# 7V_5V_3V3_Bucks.net
KiCad netlist of a schematic drawn in Altium Designer
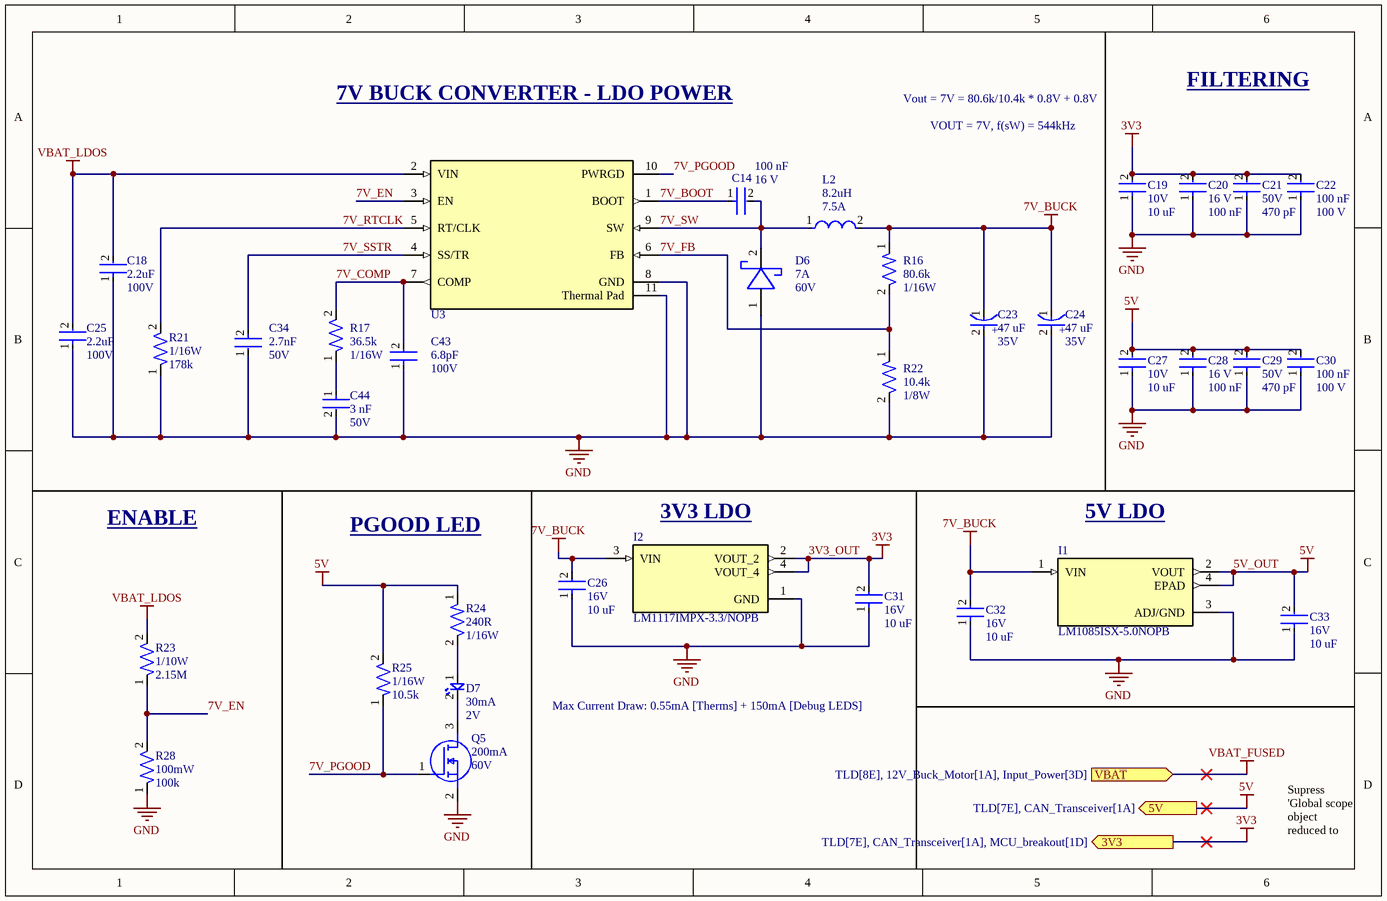
[diagram p0: 7V_5V_3V3_Bucks.SchDoc]

(export (version "E")
  (design (tool "Eeschema 10.0.6"))
  (components
    (comp (ref "C14")
      (value "CC0402KRX7R7BB104")
      (footprint "CAP-0402")
      (description "CAP CER 0.1UF 16V X7R 0402")
      (fields (field (name "VOLTAGE RATING") "16 V") (field (name "CAPACITANCE") "100 nF"))
      (libsource (lib "JLC_25") (part "CAP-0.1U-0001"))
    )
    (comp (ref "C18")
      (value "CC1206KKX7R0BB225")
      (footprint "CAP-1206")
      (description "CAP CER 2.2UF 100V X7R 1206")
      (fields (field (name "CAPACITANCE") "2.2uF") (field (name "VOLTAGE") "100V"))
      (libsource (lib "JLC_25") (part "CAP-2.2U-0001"))
    )
    (comp (ref "C19")
      (value "CC0603KRX5R6BB106")
      (footprint "CAP-0603")
      (description "CAP CER 10UF 10V X5R 0603")
      (fields (field (name "VOLTAGE") "10V") (field (name "CAPACITANCE") "10 uF"))
      (libsource (lib "JLC_25") (part "CAP-10U-0001"))
    )
    (comp (ref "C20")
      (value "CC0402KRX7R7BB104")
      (footprint "CAP-0402")
      (description "CAP CER 0.1UF 16V X7R 0402")
      (fields (field (name "VOLTAGE RATING") "16 V") (field (name "CAPACITANCE") "100 nF"))
      (libsource (lib "JLC_25") (part "CAP-0.1U-0001"))
    )
    (comp (ref "C21")
      (value "CC0805JRNPO9BN471")
      (footprint "CAP-0805")
      (description "CAP CER 470PF 50V C0G/NPO 0805")
      (fields (field (name "VOLTAGE") "50V") (field (name "CAPACITANCE") "470 pF"))
      (libsource (lib "JLC_25") (part "CAP-470P-0001"))
    )
    (comp (ref "C22")
      (value "CC0603KRX7R0BB104")
      (footprint "CAP-0603")
      (description "CAP CER 0.1UF 100V X7R 0603")
      (fields (field (name "CAPACITANCE") "100 nF") (field (name "VOLTAGE") "100 V"))
      (libsource (lib "JLC_25") (part "CAP-100N-0001"))
    )
    (comp (ref "C23")
      (value "EEH-ZC1V470P")
      (footprint "CAP-Radial-SMD")
      (description "CAP ALUM HYBRID 47UF 20% 35V SMD")
      (fields (field (name "CAPACITANCE") "47 uF") (field (name "VOLTAGE") "35V"))
      (libsource (lib "JLC_25") (part "CAP-47U-0002"))
    )
    (comp (ref "C24")
      (value "EEH-ZC1V470P")
      (footprint "CAP-Radial-SMD")
      (description "CAP ALUM HYBRID 47UF 20% 35V SMD")
      (fields (field (name "CAPACITANCE") "47 uF") (field (name "VOLTAGE") "35V"))
      (libsource (lib "JLC_25") (part "CAP-47U-0002"))
    )
    (comp (ref "C25")
      (value "CC1206KKX7R0BB225")
      (footprint "CAP-1206")
      (description "CAP CER 2.2UF 100V X7R 1206")
      (fields (field (name "CAPACITANCE") "2.2uF") (field (name "VOLTAGE") "100V"))
      (libsource (lib "JLC_25") (part "CAP-2.2U-0001"))
    )
    (comp (ref "C26")
      (value "293D106X9016A2TE3")
      (footprint "CAP-1210")
      (description "CAP TANT 10UF 10% 16V 1206")
      (fields (field (name "VOLTAGE") "16V") (field (name "CAPACITANCE") "10 uF"))
      (libsource (lib "JLC_25") (part "CAP-10U-0003_1"))
    )
    (comp (ref "C27")
      (value "CC0603KRX5R6BB106")
      (footprint "CAP-0603")
      (description "CAP CER 10UF 10V X5R 0603")
      (fields (field (name "VOLTAGE") "10V") (field (name "CAPACITANCE") "10 uF"))
      (libsource (lib "JLC_25") (part "CAP-10U-0001"))
    )
    (comp (ref "C28")
      (value "CC0402KRX7R7BB104")
      (footprint "CAP-0402")
      (description "CAP CER 0.1UF 16V X7R 0402")
      (fields (field (name "VOLTAGE RATING") "16 V") (field (name "CAPACITANCE") "100 nF"))
      (libsource (lib "JLC_25") (part "CAP-0.1U-0001"))
    )
    (comp (ref "C29")
      (value "CC0805JRNPO9BN471")
      (footprint "CAP-0805")
      (description "CAP CER 470PF 50V C0G/NPO 0805")
      (fields (field (name "VOLTAGE") "50V") (field (name "CAPACITANCE") "470 pF"))
      (libsource (lib "JLC_25") (part "CAP-470P-0001"))
    )
    (comp (ref "C30")
      (value "CC0603KRX7R0BB104")
      (footprint "CAP-0603")
      (description "CAP CER 0.1UF 100V X7R 0603")
      (fields (field (name "CAPACITANCE") "100 nF") (field (name "VOLTAGE") "100 V"))
      (libsource (lib "JLC_25") (part "CAP-100N-0001"))
    )
    (comp (ref "C31")
      (value "293D106X9016A2TE3")
      (footprint "CAP-1210")
      (description "CAP TANT 10UF 10% 16V 1206")
      (fields (field (name "VOLTAGE") "16V") (field (name "CAPACITANCE") "10 uF"))
      (libsource (lib "JLC_25") (part "CAP-10U-0003_1"))
    )
    (comp (ref "C32")
      (value "293D106X9016A2TE3")
      (footprint "CAP-1210")
      (description "CAP TANT 10UF 10% 16V 1206")
      (fields (field (name "VOLTAGE") "16V") (field (name "CAPACITANCE") "10 uF"))
      (libsource (lib "JLC_25") (part "CAP-10U-0003_1"))
    )
    (comp (ref "C33")
      (value "293D106X9016A2TE3")
      (footprint "CAP-1210")
      (description "CAP TANT 10UF 10% 16V 1206")
      (fields (field (name "VOLTAGE") "16V") (field (name "CAPACITANCE") "10 uF"))
      (libsource (lib "JLC_25") (part "CAP-10U-0003_1"))
    )
    (comp (ref "C34")
      (value "GRM2165C1H272JA01D")
      (footprint "CAP-0805")
      (description "CAP CER 2700PF 50V C0G/NP0 0805")
      (fields (field (name "VOLTAGE") "50V") (field (name "CAPACITANCE") "2.7nF"))
      (libsource (lib "JLC_25") (part "CAP-2.7N-0001"))
    )
    (comp (ref "C43")
      (value "CC0603CRNPO0BN6R8")
      (footprint "CAP-0603")
      (description "CAP CER 6.8PF 100V C0G/NPO 0603")
      (fields (field (name "VOLTAGE") "100V") (field (name "CAPACITANCE") "6.8pF"))
      (libsource (lib "JLC_25") (part "CAP-6.8P-0001"))
    )
    (comp (ref "C44")
      (value "GRM1885C1H302JA01D")
      (footprint "CAP-0603")
      (description "3000 pF ±5% 50V Ceramic Capacitor C0G, NP0 0603 (1608 Metric)")
      (fields (field (name "VOLTAGE") "50V") (field (name "CAPACITANCE") "3 nF"))
      (libsource (lib "JLC_25") (part "CAP-3N-0001"))
    )
    (comp (ref "D6")
      (value "PDS760-13")
      (footprint "DO-POWERDI5")
      (description "DIODE SCHOTTKY 60V 7A POWERDI5")
      (fields (field (name "FORWARD CURRENT") "7A") (field (name "REVERSE VOLTAGE (DC)") "60V"))
      (libsource (lib "JLC_25") (part "DIO-SCHOTTKY-0001"))
    )
    (comp (ref "D7")
      (value "BL-HKC36G-AV-TRB")
      (footprint "LED-0603")
      (description "LED YELLOW CLEAR 0603 SMD")
      (fields (field (name "FORWARD CURRENT") "30mA") (field (name "FORWARD VOLTAGE") "2V"))
      (libsource (lib "JLC_25") (part "LED-0001"))
    )
    (comp (ref "I1")
      (value "LM1085ISX-5.0NOPB")
      (footprint "IC-TO-263-4")
      (description "IC REG LIN 5V 3A DDPAK/TO263-3")
      (libsource (lib "JLC_25") (part "IC_LDO_5V_0002"))
    )
    (comp (ref "I2")
      (value "LM1117IMPX-3.3/NOPB")
      (footprint "IC-SOT-223-4")
      (description "IC REG LIN 3.3V 800MA SOT223-4")
      (libsource (lib "JLC_25") (part "IC_LDO_3V3_0001"))
    )
    (comp (ref "L2")
      (value "IHLP2525CZER8R2M01")
      (footprint "IND25X25CZ")
      (description "8.2 µH Shielded Molded Inductor 4 A 68mOhm Max Nonstandard")
      (fields (field (name "INDUCTANCE") "8.2uH") (field (name "CURRENT RATING") "7.5A"))
      (libsource (lib "JLC_25") (part "IND-8.2U-0001"))
    )
    (comp (ref "Q5")
      (value "T2N7002AK,LM")
      (footprint "IC-SOT23-3")
      (description "MOSFET N-CH 60V 200MA SOT23")
      (fields (field (name "CONTINUOUS CURRENT") "200mA") (field (name "VOLTAGE") "60V"))
      (libsource (lib "JLC_25") (part "NMOS-200MA-0001"))
    )
    (comp (ref "R16")
      (value "RC0402FR-0780K6L")
      (footprint "RES-0402")
      (description "80.6 kOhms ±1% 0.063W, 1/16W Chip Resistor 0402 (1005 Metric) Moisture Resistant Thick Film")
      (fields
        (field (name "TOLERANCE") "1%")
        (field (name "RESISTANCE") "80.6k")
        (field (name "POWER") "1/16W")
      )
      (libsource (lib "JLC_25") (part "RES-80.6k-0001"))
    )
    (comp (ref "R17")
      (value "RC0402FR-0736K5L")
      (footprint "RES-0402")
      (description "36.5 kOhms ±1% 0.063W, 1/16W Chip Resistor 0402 (1005 Metric) Moisture Resistant Thick Film")
      (fields (field (name "POWER") "1/16W") (field (name "RESISTANCE") "36.5k"))
      (libsource (lib "JLC_25") (part "RES-36.5k-0001"))
    )
    (comp (ref "R21")
      (value "RTT021783FTH")
      (footprint "RES-0402")
      (description "62.5mW Thick Film Resistors 50V ±100ppm/℃ ±1% 178kΩ 0402 Chip Resistor - Surface Mount ROHS")
      (fields
        (field (name "TOLERANCE") "1%")
        (field (name "POWER") "1/16W")
        (field (name "RESISTANCE") "178k")
      )
      (libsource (lib "JLC_25") (part "RES-178k-0001_1"))
    )
    (comp (ref "R22")
      (value "RT0805BRD0710K4L")
      (footprint "RES-0805")
      (description "10.4 kOhms ±0.1% 0.125W, 1/8W Chip Resistor 0805 (2012 Metric) Thin Film")
      (fields
        (field (name "TOLERANCE") "1%")
        (field (name "POWER") "1/8W")
        (field (name "RESISTANCE") "10.4k")
      )
      (libsource (lib "JLC_25") (part "RES-10.4k-0001"))
    )
    (comp (ref "R23")
      (value "RC0603FR-072M15L")
      (footprint "RES-0603")
      (description "RES SMD 2.15M OHM 1% 1/10W 0603")
      (fields
        (field (name "TOLERANCE") "1%")
        (field (name "POWER") "1/10W")
        (field (name "RESISTANCE") "2.15M")
      )
      (libsource (lib "JLC_25") (part "RES-2.15M-0001"))
    )
    (comp (ref "R24")
      (value "RC0402FR-07240RL")
      (footprint "RES-0402")
      (description "240R 0.063W 1% 0402 (1005 Metric)  SMD")
      (fields
        (field (name "TOLERANCE") "1%")
        (field (name "RESISTANCE") "240R")
        (field (name "POWER") "1/16W")
      )
      (libsource (lib "JLC_25") (part "RES-240-0001"))
    )
    (comp (ref "R25")
      (value "RC0402FR-0710K5L")
      (footprint "RES-0402")
      (description "RES 10.5K OHM 1% 1/16W 0402")
      (fields
        (field (name "TOLERANCE") "1%")
        (field (name "POWER") "1/16W")
        (field (name "RESISTANCE") "10.5k")
      )
      (libsource (lib "JLC_25") (part "RES-10.5k-0001"))
    )
    (comp (ref "R28")
      (value "RC0603FR-07100KL")
      (footprint "RES-0603")
      (description "RES SMD 100K OHM 1% 1/10W 0603")
      (fields
        (field (name "TOLERANCE") "1%")
        (field (name "POWER") "100mW")
        (field (name "RESISTANCE") "100k")
      )
      (libsource (lib "JLC_25") (part "RES-100k-0001"))
    )
    (comp (ref "U3")
      (value "TPS54561DPRR")
      (footprint "IC-10WSON")
      (description "IC REG BUCK ADJ 5A 10WSON")
      (libsource (lib "JLC_25") (part "IC-BUCK-0001"))
    )
  )
  (nets
    (net (code "1") (name "/7V_BOOT") (class "Default")
      (node (ref "C14") (pin "1") (pinfunction "1_1") (pintype "passive"))
      (node (ref "U3") (pin "1") (pinfunction "BOOT_1") (pintype "output"))
    )
    (net (code "2") (name "/7V_COMP") (class "Default")
      (node (ref "C43") (pin "2") (pinfunction "2_2") (pintype "passive"))
      (node (ref "R17") (pin "2") (pinfunction "2_2") (pintype "passive"))
      (node (ref "U3") (pin "7") (pinfunction "COMP_7") (pintype "output"))
    )
    (net (code "3") (name "/7V_EN") (class "Default")
      (node (ref "R23") (pin "1") (pinfunction "1_1") (pintype "passive"))
      (node (ref "R28") (pin "2") (pinfunction "2_2") (pintype "passive"))
      (node (ref "U3") (pin "3") (pinfunction "EN_3") (pintype "input"))
    )
    (net (code "4") (name "/7V_FB") (class "Default")
      (node (ref "R16") (pin "2") (pinfunction "2_2") (pintype "passive"))
      (node (ref "R22") (pin "1") (pinfunction "1_1") (pintype "passive"))
      (node (ref "U3") (pin "6") (pinfunction "FB_6") (pintype "input"))
    )
    (net (code "5") (name "/7V_PGOOD") (class "Default")
      (node (ref "Q5") (pin "1") (pinfunction "G_1") (pintype "passive"))
      (node (ref "R25") (pin "1") (pinfunction "1_1") (pintype "passive"))
      (node (ref "U3") (pin "10") (pinfunction "PWRGD_10") (pintype "open_collector"))
    )
    (net (code "6") (name "/7V_RTCLK") (class "Default")
      (node (ref "R21") (pin "2") (pinfunction "2_2") (pintype "passive"))
      (node (ref "U3") (pin "5") (pinfunction "RT/CLK_5") (pintype "input"))
    )
    (net (code "7") (name "/7V_SSTR") (class "Default")
      (node (ref "C34") (pin "2") (pinfunction "2_2") (pintype "passive"))
      (node (ref "U3") (pin "4") (pinfunction "SS/TR_4") (pintype "input"))
    )
    (net (code "8") (name "/7V_SW") (class "Default")
      (node (ref "C14") (pin "2") (pinfunction "2_2") (pintype "passive"))
      (node (ref "D6") (pin "2") (pinfunction "ANODE_2") (pintype "passive"))
      (node (ref "L2") (pin "1") (pinfunction "1_1") (pintype "passive"))
      (node (ref "U3") (pin "9") (pinfunction "SW_9") (pintype "input"))
    )
    (net (code "9") (name "3V3") (class "Default")
      (node (ref "C19") (pin "2") (pinfunction "2_2") (pintype "passive"))
      (node (ref "C20") (pin "2") (pinfunction "2_2") (pintype "passive"))
      (node (ref "C21") (pin "2") (pinfunction "2_2") (pintype "passive"))
      (node (ref "C22") (pin "2") (pinfunction "2_2") (pintype "passive"))
      (node (ref "C31") (pin "2") (pinfunction "2_2") (pintype "passive"))
      (node (ref "I2") (pin "2") (pinfunction "VOUT_2_2") (pintype "output"))
      (node (ref "I2") (pin "4") (pinfunction "VOUT_4_4") (pintype "output"))
    )
    (net (code "10") (name "5V") (class "Default")
      (node (ref "C27") (pin "2") (pinfunction "2_2") (pintype "passive"))
      (node (ref "C28") (pin "2") (pinfunction "2_2") (pintype "passive"))
      (node (ref "C29") (pin "2") (pinfunction "2_2") (pintype "passive"))
      (node (ref "C30") (pin "2") (pinfunction "2_2") (pintype "passive"))
      (node (ref "C33") (pin "2") (pinfunction "2_2") (pintype "passive"))
      (node (ref "I1") (pin "2") (pinfunction "VOUT_2") (pintype "output"))
      (node (ref "I1") (pin "4") (pinfunction "EPAD_4") (pintype "output"))
      (node (ref "R24") (pin "1") (pinfunction "1_1") (pintype "passive"))
      (node (ref "R25") (pin "2") (pinfunction "2_2") (pintype "passive"))
    )
    (net (code "11") (name "7V_BUCK") (class "Default")
      (node (ref "C23") (pin "1") (pinfunction "C_1") (pintype "passive"))
      (node (ref "C24") (pin "1") (pinfunction "C_1") (pintype "passive"))
      (node (ref "C26") (pin "2") (pinfunction "2_2") (pintype "passive"))
      (node (ref "C32") (pin "2") (pinfunction "2_2") (pintype "passive"))
      (node (ref "I1") (pin "1") (pinfunction "VIN_1") (pintype "input"))
      (node (ref "I2") (pin "3") (pinfunction "VIN_3") (pintype "input"))
      (node (ref "L2") (pin "2") (pinfunction "2_2") (pintype "passive"))
      (node (ref "R16") (pin "1") (pinfunction "1_1") (pintype "passive"))
    )
    (net (code "12") (name "GND") (class "Default")
      (node (ref "C18") (pin "1") (pinfunction "1_1") (pintype "passive"))
      (node (ref "C19") (pin "1") (pinfunction "1_1") (pintype "passive"))
      (node (ref "C20") (pin "1") (pinfunction "1_1") (pintype "passive"))
      (node (ref "C21") (pin "1") (pinfunction "1_1") (pintype "passive"))
      (node (ref "C22") (pin "1") (pinfunction "1_1") (pintype "passive"))
      (node (ref "C23") (pin "2") (pinfunction "A_2") (pintype "passive"))
      (node (ref "C24") (pin "2") (pinfunction "A_2") (pintype "passive"))
      (node (ref "C25") (pin "1") (pinfunction "1_1") (pintype "passive"))
      (node (ref "C26") (pin "1") (pinfunction "1_1") (pintype "passive"))
      (node (ref "C27") (pin "1") (pinfunction "1_1") (pintype "passive"))
      (node (ref "C28") (pin "1") (pinfunction "1_1") (pintype "passive"))
      (node (ref "C29") (pin "1") (pinfunction "1_1") (pintype "passive"))
      (node (ref "C30") (pin "1") (pinfunction "1_1") (pintype "passive"))
      (node (ref "C31") (pin "1") (pinfunction "1_1") (pintype "passive"))
      (node (ref "C32") (pin "1") (pinfunction "1_1") (pintype "passive"))
      (node (ref "C33") (pin "1") (pinfunction "1_1") (pintype "passive"))
      (node (ref "C34") (pin "1") (pinfunction "1_1") (pintype "passive"))
      (node (ref "C43") (pin "1") (pinfunction "1_1") (pintype "passive"))
      (node (ref "C44") (pin "2") (pinfunction "2_2") (pintype "passive"))
      (node (ref "D6") (pin "1") (pinfunction "CATHODE_1") (pintype "passive"))
      (node (ref "I1") (pin "3") (pinfunction "ADJ/GND_3") (pintype "power_in"))
      (node (ref "I2") (pin "1") (pinfunction "GND_1") (pintype "power_in"))
      (node (ref "Q5") (pin "2") (pinfunction "S_2") (pintype "passive"))
      (node (ref "R21") (pin "1") (pinfunction "1_1") (pintype "passive"))
      (node (ref "R22") (pin "2") (pinfunction "2_2") (pintype "passive"))
      (node (ref "R28") (pin "1") (pinfunction "1_1") (pintype "passive"))
      (node (ref "U3") (pin "11") (pinfunction "Thermal_Pad_11") (pintype "power_in"))
      (node (ref "U3") (pin "8") (pinfunction "GND_8") (pintype "power_in"))
    )
    (net (code "13") (name "Net-(C44-Pad1)") (class "Default")
      (node (ref "C44") (pin "1") (pinfunction "1_1") (pintype "passive"))
      (node (ref "R17") (pin "1") (pinfunction "1_1") (pintype "passive"))
    )
    (net (code "14") (name "Net-(D7-Pad1)") (class "Default")
      (node (ref "D7") (pin "1") (pinfunction "1_1") (pintype "passive"))
      (node (ref "R24") (pin "2") (pinfunction "2_2") (pintype "passive"))
    )
    (net (code "15") (name "Net-(Q5-D)") (class "Default")
      (node (ref "D7") (pin "2") (pinfunction "2_2") (pintype "passive"))
      (node (ref "Q5") (pin "3") (pinfunction "D_3") (pintype "passive"))
    )
    (net (code "17") (name "VBAT_LDOS") (class "Default")
      (node (ref "C18") (pin "2") (pinfunction "2_2") (pintype "passive"))
      (node (ref "C25") (pin "2") (pinfunction "2_2") (pintype "passive"))
      (node (ref "R23") (pin "2") (pinfunction "2_2") (pintype "passive"))
      (node (ref "U3") (pin "2") (pinfunction "VIN_2") (pintype "input"))
    )
  )
)
